# IO.net
KiCad netlist of a schematic drawn in Altium Designer
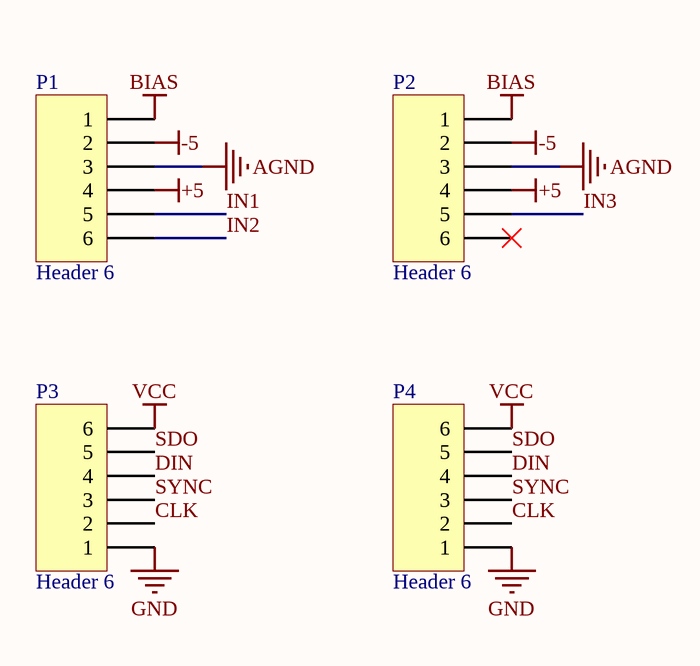
[diagram p0: IO.SchDoc]

(export (version "E")
  (design (tool "Eeschema 10.0.6"))
  (components
    (comp (ref "P1")
      (value "Header 6")
      (footprint "HDR1X6")
      (description "Header, 6-Pin")
      (fields (field (name "PUBLISHER") "Altium Limited"))
      (libsource (lib "") (part "Header 6_1"))
    )
    (comp (ref "P2")
      (value "Header 6")
      (footprint "HDR1X6")
      (description "Header, 6-Pin")
      (fields (field (name "PUBLISHER") "Altium Limited"))
      (libsource (lib "") (part "Header 6_1"))
    )
    (comp (ref "P3")
      (value "Header 6")
      (footprint "HDR1X6")
      (description "Header, 6-Pin")
      (fields (field (name "PUBLISHER") "Altium Limited"))
      (libsource (lib "Miscellaneous Connectors") (part "Header 6"))
    )
    (comp (ref "P4")
      (value "Header 6")
      (footprint "HDR1X6")
      (description "Header, 6-Pin")
      (fields (field (name "PUBLISHER") "Altium Limited"))
      (libsource (lib "Miscellaneous Connectors") (part "Header 6"))
    )
  )
  (nets
    (net (code "1") (name "+5") (class "Default")
      (node (ref "P1") (pin "4") (pinfunction "4_4") (pintype "passive"))
      (node (ref "P2") (pin "4") (pinfunction "4_4") (pintype "passive"))
    )
    (net (code "2") (name "-5") (class "Default")
      (node (ref "P1") (pin "2") (pinfunction "2_2") (pintype "passive"))
      (node (ref "P2") (pin "2") (pinfunction "2_2") (pintype "passive"))
    )
    (net (code "3") (name "/CLK") (class "Default")
      (node (ref "P3") (pin "2") (pinfunction "2_2") (pintype "passive"))
      (node (ref "P4") (pin "2") (pinfunction "2_2") (pintype "passive"))
    )
    (net (code "4") (name "/DIN") (class "Default")
      (node (ref "P3") (pin "4") (pinfunction "4_4") (pintype "passive"))
      (node (ref "P4") (pin "4") (pinfunction "4_4") (pintype "passive"))
    )
    (net (code "5") (name "/IN1") (class "Default")
      (node (ref "P1") (pin "5") (pinfunction "5_5") (pintype "passive"))
    )
    (net (code "6") (name "/IN2") (class "Default")
      (node (ref "P1") (pin "6") (pinfunction "6_6") (pintype "passive"))
    )
    (net (code "7") (name "/IN3") (class "Default")
      (node (ref "P2") (pin "5") (pinfunction "5_5") (pintype "passive"))
    )
    (net (code "8") (name "/SDO") (class "Default")
      (node (ref "P3") (pin "5") (pinfunction "5_5") (pintype "passive"))
      (node (ref "P4") (pin "5") (pinfunction "5_5") (pintype "passive"))
    )
    (net (code "9") (name "/SYNC") (class "Default")
      (node (ref "P3") (pin "3") (pinfunction "3_3") (pintype "passive"))
      (node (ref "P4") (pin "3") (pinfunction "3_3") (pintype "passive"))
    )
    (net (code "10") (name "AGND") (class "Default")
      (node (ref "P1") (pin "3") (pinfunction "3_3") (pintype "passive"))
      (node (ref "P2") (pin "3") (pinfunction "3_3") (pintype "passive"))
    )
    (net (code "11") (name "BIAS") (class "Default")
      (node (ref "P1") (pin "1") (pinfunction "1_1") (pintype "passive"))
      (node (ref "P2") (pin "1") (pinfunction "1_1") (pintype "passive"))
    )
    (net (code "12") (name "GND") (class "Default")
      (node (ref "P3") (pin "1") (pinfunction "1_1") (pintype "passive"))
      (node (ref "P4") (pin "1") (pinfunction "1_1") (pintype "passive"))
    )
    (net (code "13") (name "VCC") (class "Default")
      (node (ref "P3") (pin "6") (pinfunction "6_6") (pintype "passive"))
      (node (ref "P4") (pin "6") (pinfunction "6_6") (pintype "passive"))
    )
    (net (code "14") (name "unconnected-(P2-Pad6)") (class "Default")
      (node (ref "P2") (pin "6") (pinfunction "6_6") (pintype "passive+no_connect"))
    )
  )
)
